# Connector_0.net
KiCad netlist of a schematic drawn in Altium Designer
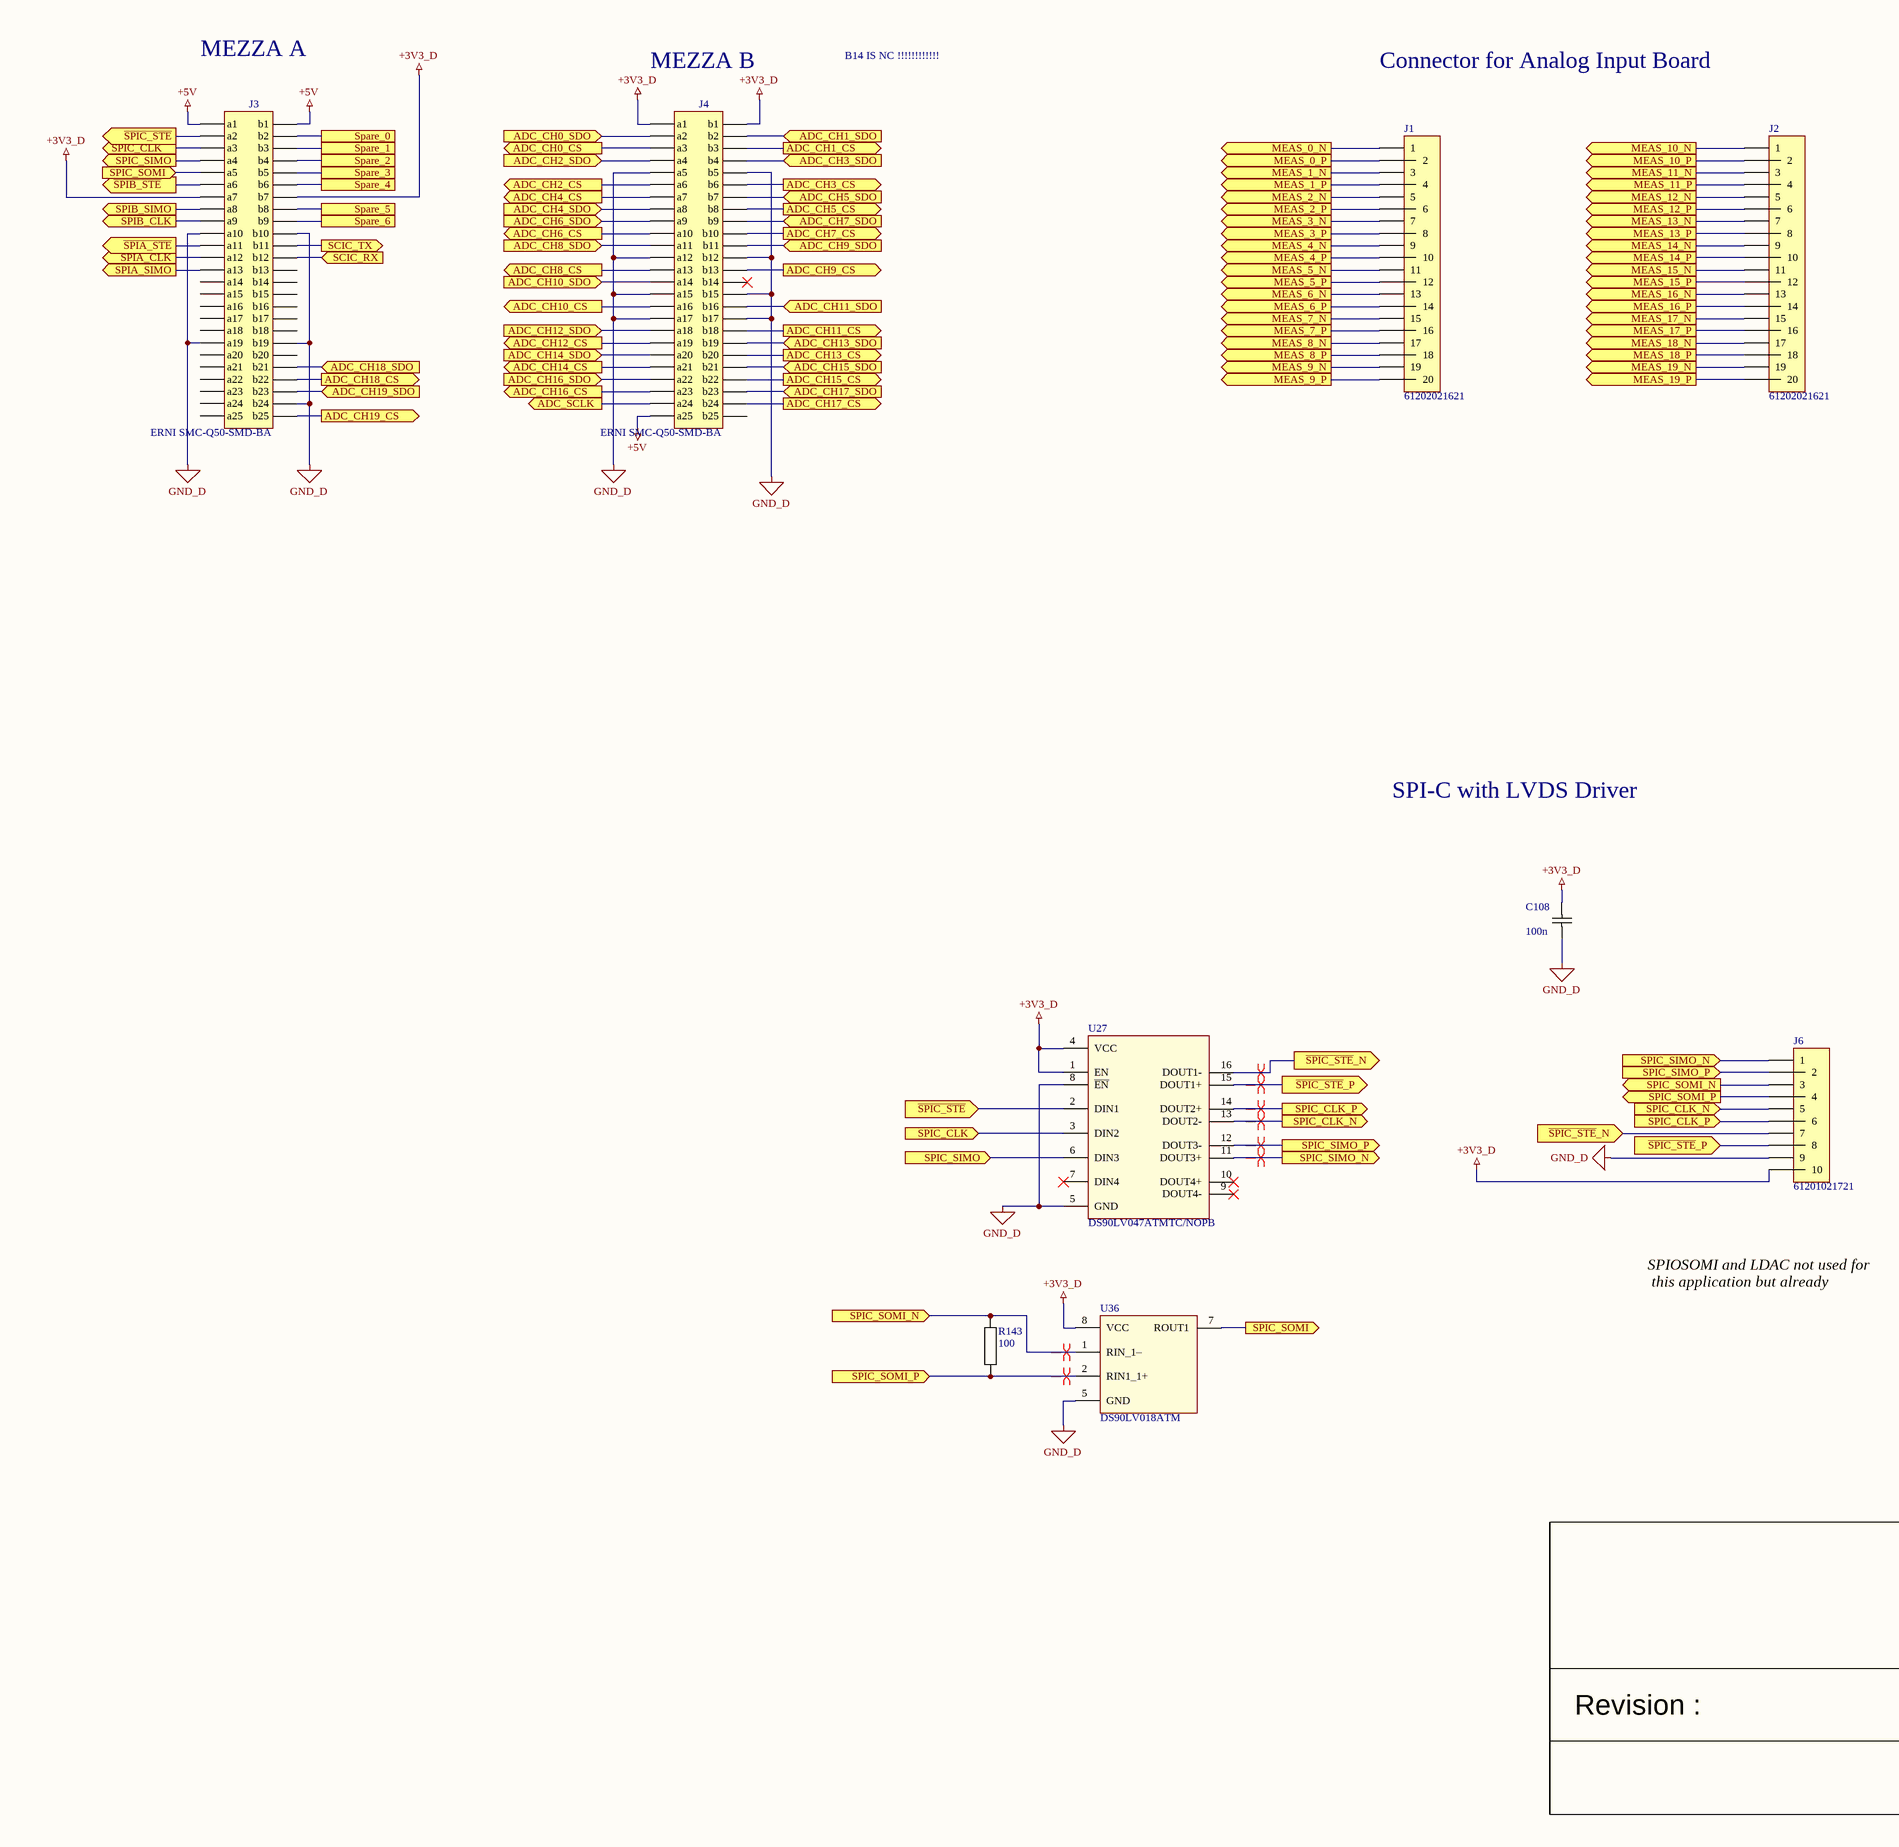
[diagram p0: Connector_0.SchDoc, left]
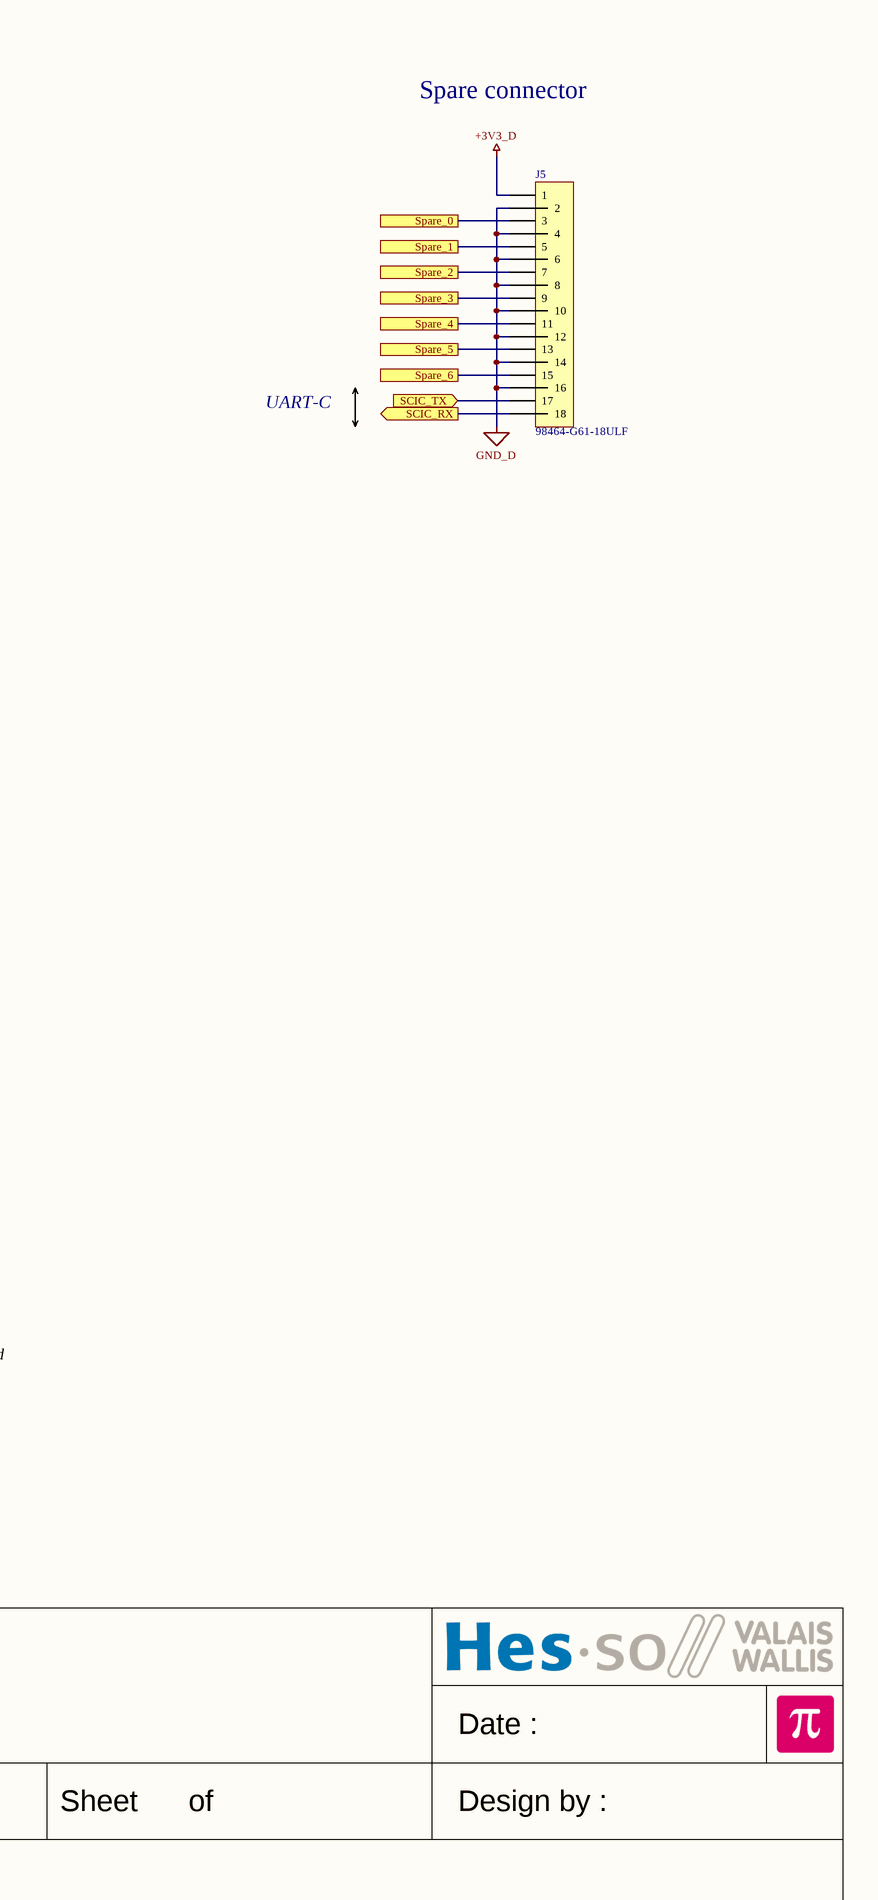
[diagram p1: Connector_0.SchDoc, right]

(export (version "E")
  (design (tool "Eeschema 10.0.6"))
  (components
    (comp (ref "C108")
      (value "100n")
      (footprint "CAPACITOR 2012 REFLOW")
      (description "Capacitor X7R 10% 50V 2012(0805)")
      (libsource (lib "Capacitor") (part "Capacitor"))
    )
    (comp (ref "J1")
      (value "61202021621")
      (footprint "FlatCable2x10 2.54MM RIGHT ANGLE TH")
      (description "FlatCable2x10")
      (fields (field (name "MANUFACTURER") "Wurth Elektronik"))
      (libsource (lib "Connector") (part "FlatCable2x10"))
    )
    (comp (ref "J2")
      (value "61202021621")
      (footprint "FlatCable2x10 2.54MM RIGHT ANGLE TH")
      (description "FlatCable2x10")
      (fields (field (name "MANUFACTURER") "Wurth Elektronik"))
      (libsource (lib "Connector") (part "FlatCable2x10"))
    )
    (comp (ref "J3")
      (value "ERNI SMC-Q50-SMD-BA")
      (footprint "ERNI SMC-Q50-SMD-BA")
      (description "Male 1.27 pitch 2x25 pin connector")
      (libsource (lib "Connector") (part "ERNI SMC-Q50-SMD-BA"))
    )
    (comp (ref "J4")
      (value "ERNI SMC-Q50-SMD-BA")
      (footprint "ERNI SMC-Q50-SMD-BA")
      (description "Male 1.27 pitch 2x25 pin connector")
      (libsource (lib "Connector") (part "ERNI SMC-Q50-SMD-BA"))
    )
    (comp (ref "J5")
      (value "98464-G61-18ULF")
      (footprint "FlatCable2x9 2MM Straight SMD FCI 98414-G52-18ALF")
      (description "FlatCable2x9")
      (fields (field (name "MANUFACTURER") "Amphenol FCI"))
      (libsource (lib "Connector") (part "FlatCable2x9"))
    )
    (comp (ref "J6")
      (value "61201021721")
      (footprint "FlatCable2x5 2.54MM Straight TH")
      (description "FlatCable2x5")
      (fields (field (name "MANUFACTURER") "Wurth Elektronik"))
      (libsource (lib "Connector") (part "FlatCable2x5"))
    )
    (comp (ref "R143")
      (value "100")
      (footprint "RESISTOR 1608 REFLOW")
      (description "Resistor 1% 50V 100mW 1608(0603)")
      (libsource (lib "Resistor") (part "Resistor"))
    )
    (comp (ref "U27")
      (value "DS90LV047ATMTC/NOPB")
      (footprint "TSSOP16 P0.65 C5.0x4.5 H1.1")
      (description "DS90LV047A 3-V LVDS Quad CMOS Differential Line Driver")
      (fields (field (name "MANUFACTURER") "Texas Instruments"))
      (libsource (lib "IntegratedCircuit") (part "DS90LV047A"))
    )
    (comp (ref "U36")
      (value "DS90LV018ATM")
      (footprint "SO8 P1.27 C4.0X5.0 H1.75")
      (description "3-V LVDS single CMOS differential line receiver")
      (libsource (lib "IntegratedCircuit") (part "DS90LV018ATM"))
    )
  )
  (nets
    (net (code "1") (name "+3V3_D") (class "Default")
      (node (ref "C108") (pin "2") (pinfunction "2_2") (pintype "passive"))
      (node (ref "J3") (pin "a7") (pinfunction "a7_a7") (pintype "passive"))
      (node (ref "J3") (pin "b7") (pinfunction "b7_b7") (pintype "passive"))
      (node (ref "J4") (pin "a1") (pinfunction "a1_a1") (pintype "passive"))
      (node (ref "J4") (pin "b1") (pinfunction "b1_b1") (pintype "passive"))
      (node (ref "J5") (pin "1") (pinfunction "1_1") (pintype "passive"))
      (node (ref "J6") (pin "10") (pinfunction "10_10") (pintype "passive"))
      (node (ref "U27") (pin "1") (pinfunction "EN_1") (pintype "passive"))
      (node (ref "U27") (pin "4") (pinfunction "VCC_4") (pintype "passive"))
      (node (ref "U36") (pin "8") (pinfunction "VCC_8") (pintype "passive"))
    )
    (net (code "2") (name "+5V") (class "Default")
      (node (ref "J3") (pin "a1") (pinfunction "a1_a1") (pintype "passive"))
      (node (ref "J3") (pin "b1") (pinfunction "b1_b1") (pintype "passive"))
      (node (ref "J4") (pin "a25") (pinfunction "a25_a25") (pintype "passive"))
    )
    (net (code "3") (name "/ADC_CH0_CS") (class "Default")
      (node (ref "J4") (pin "a3") (pinfunction "a3_a3") (pintype "passive"))
    )
    (net (code "4") (name "/ADC_CH0_SDO") (class "Default")
      (node (ref "J4") (pin "a2") (pinfunction "a2_a2") (pintype "passive"))
    )
    (net (code "5") (name "/ADC_CH1_CS") (class "Default")
      (node (ref "J4") (pin "b3") (pinfunction "b3_b3") (pintype "passive"))
    )
    (net (code "6") (name "/ADC_CH1_SDO") (class "Default")
      (node (ref "J4") (pin "b2") (pinfunction "b2_b2") (pintype "passive"))
    )
    (net (code "7") (name "/ADC_CH2_CS") (class "Default")
      (node (ref "J4") (pin "a6") (pinfunction "a6_a6") (pintype "passive"))
    )
    (net (code "8") (name "/ADC_CH2_SDO") (class "Default")
      (node (ref "J4") (pin "a4") (pinfunction "a4_a4") (pintype "passive"))
    )
    (net (code "9") (name "/ADC_CH3_CS") (class "Default")
      (node (ref "J4") (pin "b6") (pinfunction "b6_b6") (pintype "passive"))
    )
    (net (code "10") (name "/ADC_CH3_SDO") (class "Default")
      (node (ref "J4") (pin "b4") (pinfunction "b4_b4") (pintype "passive"))
    )
    (net (code "11") (name "/ADC_CH4_CS") (class "Default")
      (node (ref "J4") (pin "a7") (pinfunction "a7_a7") (pintype "passive"))
    )
    (net (code "12") (name "/ADC_CH4_SDO") (class "Default")
      (node (ref "J4") (pin "a8") (pinfunction "a8_a8") (pintype "passive"))
    )
    (net (code "13") (name "/ADC_CH5_CS") (class "Default")
      (node (ref "J4") (pin "b8") (pinfunction "b8_b8") (pintype "passive"))
    )
    (net (code "14") (name "/ADC_CH5_SDO") (class "Default")
      (node (ref "J4") (pin "b7") (pinfunction "b7_b7") (pintype "passive"))
    )
    (net (code "15") (name "/ADC_CH6_CS") (class "Default")
      (node (ref "J4") (pin "a10") (pinfunction "a10_a10") (pintype "passive"))
    )
    (net (code "16") (name "/ADC_CH6_SDO") (class "Default")
      (node (ref "J4") (pin "a9") (pinfunction "a9_a9") (pintype "passive"))
    )
    (net (code "17") (name "/ADC_CH7_CS") (class "Default")
      (node (ref "J4") (pin "b10") (pinfunction "b10_b10") (pintype "passive"))
    )
    (net (code "18") (name "/ADC_CH7_SDO") (class "Default")
      (node (ref "J4") (pin "b9") (pinfunction "b9_b9") (pintype "passive"))
    )
    (net (code "19") (name "/ADC_CH8_CS") (class "Default")
      (node (ref "J4") (pin "a13") (pinfunction "a13_a13") (pintype "passive"))
    )
    (net (code "20") (name "/ADC_CH8_SDO") (class "Default")
      (node (ref "J4") (pin "a11") (pinfunction "a11_a11") (pintype "passive"))
    )
    (net (code "21") (name "/ADC_CH9_CS") (class "Default")
      (node (ref "J4") (pin "b13") (pinfunction "b13_b13") (pintype "passive"))
    )
    (net (code "22") (name "/ADC_CH9_SDO") (class "Default")
      (node (ref "J4") (pin "b11") (pinfunction "b11_b11") (pintype "passive"))
    )
    (net (code "23") (name "/ADC_CH10_CS") (class "Default")
      (node (ref "J4") (pin "a16") (pinfunction "a16_a16") (pintype "passive"))
    )
    (net (code "24") (name "/ADC_CH10_SDO") (class "Default")
      (node (ref "J4") (pin "a14") (pinfunction "a14_a14") (pintype "passive"))
    )
    (net (code "25") (name "/ADC_CH11_CS") (class "Default")
      (node (ref "J4") (pin "b18") (pinfunction "b18_b18") (pintype "passive"))
    )
    (net (code "26") (name "/ADC_CH11_SDO") (class "Default")
      (node (ref "J4") (pin "b16") (pinfunction "b16_b16") (pintype "passive"))
    )
    (net (code "27") (name "/ADC_CH12_CS") (class "Default")
      (node (ref "J4") (pin "a19") (pinfunction "a19_a19") (pintype "passive"))
    )
    (net (code "28") (name "/ADC_CH12_SDO") (class "Default")
      (node (ref "J4") (pin "a18") (pinfunction "a18_a18") (pintype "passive"))
    )
    (net (code "29") (name "/ADC_CH13_CS") (class "Default")
      (node (ref "J4") (pin "b20") (pinfunction "b20_b20") (pintype "passive"))
    )
    (net (code "30") (name "/ADC_CH13_SDO") (class "Default")
      (node (ref "J4") (pin "b19") (pinfunction "b19_b19") (pintype "passive"))
    )
    (net (code "31") (name "/ADC_CH14_CS") (class "Default")
      (node (ref "J4") (pin "a21") (pinfunction "a21_a21") (pintype "passive"))
    )
    (net (code "32") (name "/ADC_CH14_SDO") (class "Default")
      (node (ref "J4") (pin "a20") (pinfunction "a20_a20") (pintype "passive"))
    )
    (net (code "33") (name "/ADC_CH15_CS") (class "Default")
      (node (ref "J4") (pin "b22") (pinfunction "b22_b22") (pintype "passive"))
    )
    (net (code "34") (name "/ADC_CH15_SDO") (class "Default")
      (node (ref "J4") (pin "b21") (pinfunction "b21_b21") (pintype "passive"))
    )
    (net (code "35") (name "/ADC_CH16_CS") (class "Default")
      (node (ref "J4") (pin "a23") (pinfunction "a23_a23") (pintype "passive"))
    )
    (net (code "36") (name "/ADC_CH16_SDO") (class "Default")
      (node (ref "J4") (pin "a22") (pinfunction "a22_a22") (pintype "passive"))
    )
    (net (code "37") (name "/ADC_CH17_CS") (class "Default")
      (node (ref "J4") (pin "b24") (pinfunction "b24_b24") (pintype "passive"))
    )
    (net (code "38") (name "/ADC_CH17_SDO") (class "Default")
      (node (ref "J4") (pin "b23") (pinfunction "b23_b23") (pintype "passive"))
    )
    (net (code "39") (name "/ADC_CH18_CS") (class "Default")
      (node (ref "J3") (pin "b22") (pinfunction "b22_b22") (pintype "passive"))
    )
    (net (code "40") (name "/ADC_CH18_SDO") (class "Default")
      (node (ref "J3") (pin "b21") (pinfunction "b21_b21") (pintype "passive"))
    )
    (net (code "41") (name "/ADC_CH19_CS") (class "Default")
      (node (ref "J3") (pin "b25") (pinfunction "b25_b25") (pintype "passive"))
    )
    (net (code "42") (name "/ADC_CH19_SDO") (class "Default")
      (node (ref "J3") (pin "b23") (pinfunction "b23_b23") (pintype "passive"))
    )
    (net (code "43") (name "/ADC_SCLK") (class "Default")
      (node (ref "J4") (pin "a24") (pinfunction "a24_a24") (pintype "passive"))
    )
    (net (code "44") (name "/MEAS_0_N") (class "Default")
      (node (ref "J1") (pin "1") (pinfunction "1_1") (pintype "passive"))
    )
    (net (code "45") (name "/MEAS_0_P") (class "Default")
      (node (ref "J1") (pin "2") (pinfunction "2_2") (pintype "passive"))
    )
    (net (code "46") (name "/MEAS_1_N") (class "Default")
      (node (ref "J1") (pin "3") (pinfunction "3_3") (pintype "passive"))
    )
    (net (code "47") (name "/MEAS_1_P") (class "Default")
      (node (ref "J1") (pin "4") (pinfunction "4_4") (pintype "passive"))
    )
    (net (code "48") (name "/MEAS_2_N") (class "Default")
      (node (ref "J1") (pin "5") (pinfunction "5_5") (pintype "passive"))
    )
    (net (code "49") (name "/MEAS_2_P") (class "Default")
      (node (ref "J1") (pin "6") (pinfunction "6_6") (pintype "passive"))
    )
    (net (code "50") (name "/MEAS_3_N") (class "Default")
      (node (ref "J1") (pin "7") (pinfunction "7_7") (pintype "passive"))
    )
    (net (code "51") (name "/MEAS_3_P") (class "Default")
      (node (ref "J1") (pin "8") (pinfunction "8_8") (pintype "passive"))
    )
    (net (code "52") (name "/MEAS_4_N") (class "Default")
      (node (ref "J1") (pin "9") (pinfunction "9_9") (pintype "passive"))
    )
    (net (code "53") (name "/MEAS_4_P") (class "Default")
      (node (ref "J1") (pin "10") (pinfunction "10_10") (pintype "passive"))
    )
    (net (code "54") (name "/MEAS_5_N") (class "Default")
      (node (ref "J1") (pin "11") (pinfunction "11_11") (pintype "passive"))
    )
    (net (code "55") (name "/MEAS_5_P") (class "Default")
      (node (ref "J1") (pin "12") (pinfunction "12_12") (pintype "passive"))
    )
    (net (code "56") (name "/MEAS_6_N") (class "Default")
      (node (ref "J1") (pin "13") (pinfunction "13_13") (pintype "passive"))
    )
    (net (code "57") (name "/MEAS_6_P") (class "Default")
      (node (ref "J1") (pin "14") (pinfunction "14_14") (pintype "passive"))
    )
    (net (code "58") (name "/MEAS_7_N") (class "Default")
      (node (ref "J1") (pin "15") (pinfunction "15_15") (pintype "passive"))
    )
    (net (code "59") (name "/MEAS_7_P") (class "Default")
      (node (ref "J1") (pin "16") (pinfunction "16_16") (pintype "passive"))
    )
    (net (code "60") (name "/MEAS_8_N") (class "Default")
      (node (ref "J1") (pin "17") (pinfunction "17_17") (pintype "passive"))
    )
    (net (code "61") (name "/MEAS_8_P") (class "Default")
      (node (ref "J1") (pin "18") (pinfunction "18_18") (pintype "passive"))
    )
    (net (code "62") (name "/MEAS_9_N") (class "Default")
      (node (ref "J1") (pin "19") (pinfunction "19_19") (pintype "passive"))
    )
    (net (code "63") (name "/MEAS_9_P") (class "Default")
      (node (ref "J1") (pin "20") (pinfunction "20_20") (pintype "passive"))
    )
    (net (code "64") (name "/MEAS_10_N") (class "Default")
      (node (ref "J2") (pin "1") (pinfunction "1_1") (pintype "passive"))
    )
    (net (code "65") (name "/MEAS_10_P") (class "Default")
      (node (ref "J2") (pin "2") (pinfunction "2_2") (pintype "passive"))
    )
    (net (code "66") (name "/MEAS_11_N") (class "Default")
      (node (ref "J2") (pin "3") (pinfunction "3_3") (pintype "passive"))
    )
    (net (code "67") (name "/MEAS_11_P") (class "Default")
      (node (ref "J2") (pin "4") (pinfunction "4_4") (pintype "passive"))
    )
    (net (code "68") (name "/MEAS_12_N") (class "Default")
      (node (ref "J2") (pin "5") (pinfunction "5_5") (pintype "passive"))
    )
    (net (code "69") (name "/MEAS_12_P") (class "Default")
      (node (ref "J2") (pin "6") (pinfunction "6_6") (pintype "passive"))
    )
    (net (code "70") (name "/MEAS_13_N") (class "Default")
      (node (ref "J2") (pin "7") (pinfunction "7_7") (pintype "passive"))
    )
    (net (code "71") (name "/MEAS_13_P") (class "Default")
      (node (ref "J2") (pin "8") (pinfunction "8_8") (pintype "passive"))
    )
    (net (code "72") (name "/MEAS_14_N") (class "Default")
      (node (ref "J2") (pin "9") (pinfunction "9_9") (pintype "passive"))
    )
    (net (code "73") (name "/MEAS_14_P") (class "Default")
      (node (ref "J2") (pin "10") (pinfunction "10_10") (pintype "passive"))
    )
    (net (code "74") (name "/MEAS_15_N") (class "Default")
      (node (ref "J2") (pin "11") (pinfunction "11_11") (pintype "passive"))
    )
    (net (code "75") (name "/MEAS_15_P") (class "Default")
      (node (ref "J2") (pin "12") (pinfunction "12_12") (pintype "passive"))
    )
    (net (code "76") (name "/MEAS_16_N") (class "Default")
      (node (ref "J2") (pin "13") (pinfunction "13_13") (pintype "passive"))
    )
    (net (code "77") (name "/MEAS_16_P") (class "Default")
      (node (ref "J2") (pin "14") (pinfunction "14_14") (pintype "passive"))
    )
    (net (code "78") (name "/MEAS_17_N") (class "Default")
      (node (ref "J2") (pin "15") (pinfunction "15_15") (pintype "passive"))
    )
    (net (code "79") (name "/MEAS_17_P") (class "Default")
      (node (ref "J2") (pin "16") (pinfunction "16_16") (pintype "passive"))
    )
    (net (code "80") (name "/MEAS_18_N") (class "Default")
      (node (ref "J2") (pin "17") (pinfunction "17_17") (pintype "passive"))
    )
    (net (code "81") (name "/MEAS_18_P") (class "Default")
      (node (ref "J2") (pin "18") (pinfunction "18_18") (pintype "passive"))
    )
    (net (code "82") (name "/MEAS_19_N") (class "Default")
      (node (ref "J2") (pin "19") (pinfunction "19_19") (pintype "passive"))
    )
    (net (code "83") (name "/MEAS_19_P") (class "Default")
      (node (ref "J2") (pin "20") (pinfunction "20_20") (pintype "passive"))
    )
    (net (code "84") (name "/SCIC_RX") (class "Default")
      (node (ref "J3") (pin "b12") (pinfunction "b12_b12") (pintype "passive"))
      (node (ref "J5") (pin "18") (pinfunction "18_18") (pintype "passive"))
    )
    (net (code "85") (name "/SCIC_TX") (class "Default")
      (node (ref "J3") (pin "b11") (pinfunction "b11_b11") (pintype "passive"))
      (node (ref "J5") (pin "17") (pinfunction "17_17") (pintype "passive"))
    )
    (net (code "86") (name "/SPIA_CLK") (class "Default")
      (node (ref "J3") (pin "a12") (pinfunction "a12_a12") (pintype "passive"))
    )
    (net (code "87") (name "/SPIA_SIMO") (class "Default")
      (node (ref "J3") (pin "a13") (pinfunction "a13_a13") (pintype "passive"))
    )
    (net (code "88") (name "/SPIB_CLK") (class "Default")
      (node (ref "J3") (pin "a9") (pinfunction "a9_a9") (pintype "passive"))
    )
    (net (code "89") (name "/SPIB_SIMO") (class "Default")
      (node (ref "J3") (pin "a8") (pinfunction "a8_a8") (pintype "passive"))
    )
    (net (code "90") (name "/SPIC_CLK") (class "Default")
      (node (ref "J3") (pin "a3") (pinfunction "a3_a3") (pintype "passive"))
      (node (ref "U27") (pin "3") (pinfunction "DIN2_3") (pintype "passive"))
    )
    (net (code "91") (name "/SPIC_CLK_N") (class "Default")
      (node (ref "J6") (pin "5") (pinfunction "5_5") (pintype "passive"))
      (node (ref "U27") (pin "13") (pinfunction "DOUT2-_13") (pintype "passive"))
    )
    (net (code "92") (name "/SPIC_CLK_P") (class "Default")
      (node (ref "J6") (pin "6") (pinfunction "6_6") (pintype "passive"))
      (node (ref "U27") (pin "14") (pinfunction "DOUT2+_14") (pintype "passive"))
    )
    (net (code "93") (name "/SPIC_SIMO") (class "Default")
      (node (ref "J3") (pin "a4") (pinfunction "a4_a4") (pintype "passive"))
      (node (ref "U27") (pin "6") (pinfunction "DIN3_6") (pintype "passive"))
    )
    (net (code "94") (name "/SPIC_SIMO_N") (class "Default")
      (node (ref "J6") (pin "1") (pinfunction "1_1") (pintype "passive"))
      (node (ref "U27") (pin "11") (pinfunction "DOUT3+_11") (pintype "passive"))
    )
    (net (code "95") (name "/SPIC_SIMO_P") (class "Default")
      (node (ref "J6") (pin "2") (pinfunction "2_2") (pintype "passive"))
      (node (ref "U27") (pin "12") (pinfunction "DOUT3-_12") (pintype "passive"))
    )
    (net (code "96") (name "/SPIC_SOMI") (class "Default")
      (node (ref "J3") (pin "a5") (pinfunction "a5_a5") (pintype "passive"))
      (node (ref "U36") (pin "7") (pinfunction "ROUT1_7") (pintype "passive"))
    )
    (net (code "97") (name "/SPIC_SOMI_N") (class "Default")
      (node (ref "J6") (pin "3") (pinfunction "3_3") (pintype "passive"))
      (node (ref "R143") (pin "1") (pinfunction "1_1") (pintype "passive"))
      (node (ref "U36") (pin "1") (pinfunction "RIN_1–_1") (pintype "passive"))
    )
    (net (code "98") (name "/SPIC_SOMI_P") (class "Default")
      (node (ref "J6") (pin "4") (pinfunction "4_4") (pintype "passive"))
      (node (ref "R143") (pin "2") (pinfunction "2_2") (pintype "passive"))
      (node (ref "U36") (pin "2") (pinfunction "RIN1_1+_2") (pintype "passive"))
    )
    (net (code "99") (name "/Spare_0") (class "Default")
      (node (ref "J3") (pin "b2") (pinfunction "b2_b2") (pintype "passive"))
      (node (ref "J5") (pin "3") (pinfunction "3_3") (pintype "passive"))
    )
    (net (code "100") (name "/Spare_1") (class "Default")
      (node (ref "J3") (pin "b3") (pinfunction "b3_b3") (pintype "passive"))
      (node (ref "J5") (pin "5") (pinfunction "5_5") (pintype "passive"))
    )
    (net (code "101") (name "/Spare_2") (class "Default")
      (node (ref "J3") (pin "b4") (pinfunction "b4_b4") (pintype "passive"))
      (node (ref "J5") (pin "7") (pinfunction "7_7") (pintype "passive"))
    )
    (net (code "102") (name "/Spare_3") (class "Default")
      (node (ref "J3") (pin "b5") (pinfunction "b5_b5") (pintype "passive"))
      (node (ref "J5") (pin "9") (pinfunction "9_9") (pintype "passive"))
    )
    (net (code "103") (name "/Spare_4") (class "Default")
      (node (ref "J3") (pin "b6") (pinfunction "b6_b6") (pintype "passive"))
      (node (ref "J5") (pin "11") (pinfunction "11_11") (pintype "passive"))
    )
    (net (code "104") (name "/Spare_5") (class "Default")
      (node (ref "J3") (pin "b8") (pinfunction "b8_b8") (pintype "passive"))
      (node (ref "J5") (pin "13") (pinfunction "13_13") (pintype "passive"))
    )
    (net (code "105") (name "/Spare_6") (class "Default")
      (node (ref "J3") (pin "b9") (pinfunction "b9_b9") (pintype "passive"))
      (node (ref "J5") (pin "15") (pinfunction "15_15") (pintype "passive"))
    )
    (net (code "106") (name "/~{SPIA_STE}") (class "Default")
      (node (ref "J3") (pin "a11") (pinfunction "a11_a11") (pintype "passive"))
    )
    (net (code "107") (name "/~{SPIB_STE}") (class "Default")
      (node (ref "J3") (pin "a6") (pinfunction "a6_a6") (pintype "passive"))
    )
    (net (code "108") (name "/~{SPIC_STE}") (class "Default")
      (node (ref "J3") (pin "a2") (pinfunction "a2_a2") (pintype "passive"))
      (node (ref "U27") (pin "2") (pinfunction "DIN1_2") (pintype "passive"))
    )
    (net (code "109") (name "/~{SPIC_STE}_N") (class "Default")
      (node (ref "J6") (pin "7") (pinfunction "7_7") (pintype "passive"))
      (node (ref "U27") (pin "16") (pinfunction "DOUT1-_16") (pintype "passive"))
    )
    (net (code "110") (name "/~{SPIC_STE}_P") (class "Default")
      (node (ref "J6") (pin "8") (pinfunction "8_8") (pintype "passive"))
      (node (ref "U27") (pin "15") (pinfunction "DOUT1+_15") (pintype "passive"))
    )
    (net (code "111") (name "GND_D") (class "Default")
      (node (ref "C108") (pin "1") (pinfunction "1_1") (pintype "passive"))
      (node (ref "J3") (pin "a10") (pinfunction "a10_a10") (pintype "passive"))
      (node (ref "J3") (pin "a19") (pinfunction "a19_a19") (pintype "passive"))
      (node (ref "J3") (pin "b10") (pinfunction "b10_b10") (pintype "passive"))
      (node (ref "J3") (pin "b19") (pinfunction "b19_b19") (pintype "passive"))
      (node (ref "J3") (pin "b24") (pinfunction "b24_b24") (pintype "passive"))
      (node (ref "J4") (pin "a12") (pinfunction "a12_a12") (pintype "passive"))
      (node (ref "J4") (pin "a15") (pinfunction "a15_a15") (pintype "passive"))
      (node (ref "J4") (pin "a17") (pinfunction "a17_a17") (pintype "passive"))
      (node (ref "J4") (pin "a5") (pinfunction "a5_a5") (pintype "passive"))
      (node (ref "J4") (pin "b12") (pinfunction "b12_b12") (pintype "passive"))
      (node (ref "J4") (pin "b15") (pinfunction "b15_b15") (pintype "passive"))
      (node (ref "J4") (pin "b17") (pinfunction "b17_b17") (pintype "passive"))
      (node (ref "J4") (pin "b5") (pinfunction "b5_b5") (pintype "passive"))
      (node (ref "J5") (pin "10") (pinfunction "10_10") (pintype "passive"))
      (node (ref "J5") (pin "12") (pinfunction "12_12") (pintype "passive"))
      (node (ref "J5") (pin "14") (pinfunction "14_14") (pintype "passive"))
      (node (ref "J5") (pin "16") (pinfunction "16_16") (pintype "passive"))
      (node (ref "J5") (pin "2") (pinfunction "2_2") (pintype "passive"))
      (node (ref "J5") (pin "4") (pinfunction "4_4") (pintype "passive"))
      (node (ref "J5") (pin "6") (pinfunction "6_6") (pintype "passive"))
      (node (ref "J5") (pin "8") (pinfunction "8_8") (pintype "passive"))
      (node (ref "J6") (pin "9") (pinfunction "9_9") (pintype "passive"))
      (node (ref "U27") (pin "5") (pinfunction "GND_5") (pintype "passive"))
      (node (ref "U27") (pin "8") (pinfunction "~{EN}_8") (pintype "passive"))
      (node (ref "U36") (pin "5") (pinfunction "GND_5") (pintype "passive"))
    )
    (net (code "112") (name "unconnected-(J3-Pada14)") (class "Default")
      (node (ref "J3") (pin "a14") (pinfunction "a14_a14") (pintype "passive"))
    )
    (net (code "113") (name "unconnected-(J3-Pada15)") (class "Default")
      (node (ref "J3") (pin "a15") (pinfunction "a15_a15") (pintype "passive"))
    )
    (net (code "114") (name "unconnected-(J3-Pada16)") (class "Default")
      (node (ref "J3") (pin "a16") (pinfunction "a16_a16") (pintype "passive"))
    )
    (net (code "115") (name "unconnected-(J3-Pada17)") (class "Default")
      (node (ref "J3") (pin "a17") (pinfunction "a17_a17") (pintype "passive"))
    )
    (net (code "116") (name "unconnected-(J3-Pada18)") (class "Default")
      (node (ref "J3") (pin "a18") (pinfunction "a18_a18") (pintype "passive"))
    )
    (net (code "117") (name "unconnected-(J3-Pada20)") (class "Default")
      (node (ref "J3") (pin "a20") (pinfunction "a20_a20") (pintype "passive"))
    )
    (net (code "118") (name "unconnected-(J3-Pada21)") (class "Default")
      (node (ref "J3") (pin "a21") (pinfunction "a21_a21") (pintype "passive"))
    )
    (net (code "119") (name "unconnected-(J3-Pada22)") (class "Default")
      (node (ref "J3") (pin "a22") (pinfunction "a22_a22") (pintype "passive"))
    )
    (net (code "120") (name "unconnected-(J3-Pada23)") (class "Default")
      (node (ref "J3") (pin "a23") (pinfunction "a23_a23") (pintype "passive"))
    )
    (net (code "121") (name "unconnected-(J3-Pada24)") (class "Default")
      (node (ref "J3") (pin "a24") (pinfunction "a24_a24") (pintype "passive"))
    )
    (net (code "122") (name "unconnected-(J3-Pada25)") (class "Default")
      (node (ref "J3") (pin "a25") (pinfunction "a25_a25") (pintype "passive"))
    )
    (net (code "123") (name "unconnected-(J3-Padb13)") (class "Default")
      (node (ref "J3") (pin "b13") (pinfunction "b13_b13") (pintype "passive"))
    )
    (net (code "124") (name "unconnected-(J3-Padb14)") (class "Default")
      (node (ref "J3") (pin "b14") (pinfunction "b14_b14") (pintype "passive"))
    )
    (net (code "125") (name "unconnected-(J3-Padb15)") (class "Default")
      (node (ref "J3") (pin "b15") (pinfunction "b15_b15") (pintype "passive"))
    )
    (net (code "126") (name "unconnected-(J3-Padb16)") (class "Default")
      (node (ref "J3") (pin "b16") (pinfunction "b16_b16") (pintype "passive"))
    )
    (net (code "127") (name "unconnected-(J3-Padb17)") (class "Default")
      (node (ref "J3") (pin "b17") (pinfunction "b17_b17") (pintype "passive"))
    )
    (net (code "128") (name "unconnected-(J3-Padb18)") (class "Default")
      (node (ref "J3") (pin "b18") (pinfunction "b18_b18") (pintype "passive"))
    )
    (net (code "129") (name "unconnected-(J3-Padb20)") (class "Default")
      (node (ref "J3") (pin "b20") (pinfunction "b20_b20") (pintype "passive"))
    )
    (net (code "130") (name "unconnected-(J4-Padb14)") (class "Default")
      (node (ref "J4") (pin "b14") (pinfunction "b14_b14") (pintype "passive+no_connect"))
    )
    (net (code "131") (name "unconnected-(J4-Padb25)") (class "Default")
      (node (ref "J4") (pin "b25") (pinfunction "b25_b25") (pintype "passive"))
    )
    (net (code "132") (name "unconnected-(U27-DIN4-Pad7)") (class "Default")
      (node (ref "U27") (pin "7") (pinfunction "DIN4_7") (pintype "passive+no_connect"))
    )
    (net (code "133") (name "unconnected-(U27-DOUT4+-Pad10)") (class "Default")
      (node (ref "U27") (pin "10") (pinfunction "DOUT4+_10") (pintype "passive+no_connect"))
    )
    (net (code "134") (name "unconnected-(U27-DOUT4--Pad9)") (class "Default")
      (node (ref "U27") (pin "9") (pinfunction "DOUT4-_9") (pintype "passive+no_connect"))
    )
  )
)
